# Indication.net
KiCad netlist of a schematic drawn in Altium Designer
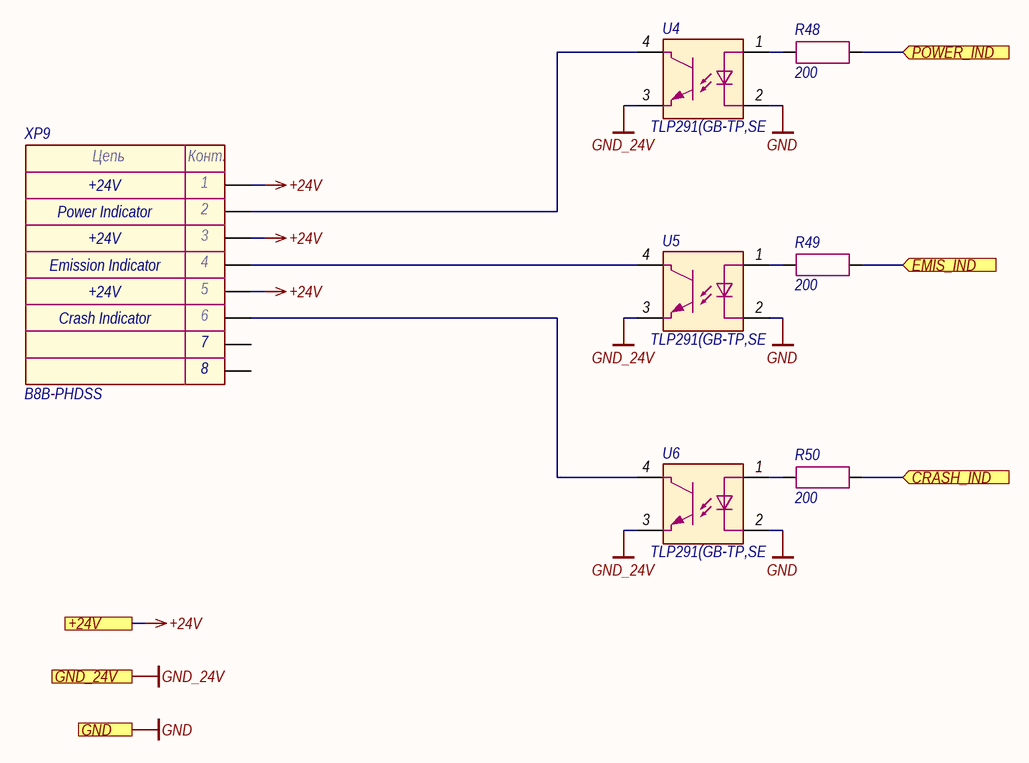
[diagram p0: Indication.SchDoc]

(export (version "E")
  (design (tool "Eeschema 10.0.6"))
  (components
    (comp (ref "R48")
      (value "200")
      (footprint "Pcb_library:RES_0603")
      (fields (field (name "MANUFACTURER") "Yageo"))
      (libsource (lib "Schem_library") (part "Resistor"))
    )
    (comp (ref "R49")
      (value "200")
      (footprint "Pcb_library:RES_0603")
      (fields (field (name "MANUFACTURER") "Yageo"))
      (libsource (lib "Schem_library") (part "Resistor"))
    )
    (comp (ref "R50")
      (value "200")
      (footprint "Pcb_library:RES_0603")
      (fields (field (name "MANUFACTURER") "Yageo"))
      (libsource (lib "Schem_library") (part "Resistor"))
    )
    (comp (ref "U4")
      (value "TLP291(GB-TP,SE")
      (footprint "Pcb_library:11-3C1")
      (fields (field (name "MANUFACTURER") "Toshiba"))
      (libsource (lib "Schem_library") (part "TLP291"))
    )
    (comp (ref "U5")
      (value "TLP291(GB-TP,SE")
      (footprint "Pcb_library:11-3C1")
      (fields (field (name "MANUFACTURER") "Toshiba"))
      (libsource (lib "Schem_library") (part "TLP291"))
    )
    (comp (ref "U6")
      (value "TLP291(GB-TP,SE")
      (footprint "Pcb_library:11-3C1")
      (fields (field (name "MANUFACTURER") "Toshiba"))
      (libsource (lib "Schem_library") (part "TLP291"))
    )
    (comp (ref "XP9")
      (value "B8B-PHDSS")
      (footprint "Pcb_library:B8B-PHDSS")
      (fields (field (name "MANUFACTURER") "JST"))
      (libsource (lib "Schem_library") (part "Connector-8"))
    )
  )
  (nets
    (net (code "1") (name "+24V") (class "Default")
      (node (ref "XP9") (pin "1") (pintype "passive"))
      (node (ref "XP9") (pin "3") (pintype "passive"))
      (node (ref "XP9") (pin "5") (pintype "passive"))
    )
    (net (code "2") (name "/CRASH_IND") (class "Default")
      (node (ref "R50") (pin "2") (pinfunction "2_2") (pintype "passive"))
    )
    (net (code "3") (name "/EMIS_IND") (class "Default")
      (node (ref "R49") (pin "2") (pinfunction "2_2") (pintype "passive"))
    )
    (net (code "4") (name "/POWER_IND") (class "Default")
      (node (ref "R48") (pin "2") (pinfunction "2_2") (pintype "passive"))
    )
    (net (code "5") (name "GND") (class "Default")
      (node (ref "U4") (pin "2") (pintype "passive"))
      (node (ref "U5") (pin "2") (pintype "passive"))
      (node (ref "U6") (pin "2") (pintype "passive"))
    )
    (net (code "6") (name "GND_24V") (class "Default")
      (node (ref "U4") (pin "3") (pintype "passive"))
      (node (ref "U5") (pin "3") (pintype "passive"))
      (node (ref "U6") (pin "3") (pintype "passive"))
    )
    (net (code "7") (name "Net-(R48-Pad1)") (class "Default")
      (node (ref "R48") (pin "1") (pinfunction "1_1") (pintype "passive"))
      (node (ref "U4") (pin "1") (pintype "passive"))
    )
    (net (code "8") (name "Net-(R49-Pad1)") (class "Default")
      (node (ref "R49") (pin "1") (pinfunction "1_1") (pintype "passive"))
      (node (ref "U5") (pin "1") (pintype "passive"))
    )
    (net (code "9") (name "Net-(R50-Pad1)") (class "Default")
      (node (ref "R50") (pin "1") (pinfunction "1_1") (pintype "passive"))
      (node (ref "U6") (pin "1") (pintype "passive"))
    )
    (net (code "10") (name "Net-(U4-Pad4)") (class "Default")
      (node (ref "U4") (pin "4") (pintype "passive"))
      (node (ref "XP9") (pin "2") (pintype "passive"))
    )
    (net (code "11") (name "Net-(U5-Pad4)") (class "Default")
      (node (ref "U5") (pin "4") (pintype "passive"))
      (node (ref "XP9") (pin "4") (pintype "passive"))
    )
    (net (code "12") (name "Net-(U6-Pad4)") (class "Default")
      (node (ref "U6") (pin "4") (pintype "passive"))
      (node (ref "XP9") (pin "6") (pintype "passive"))
    )
    (net (code "13") (name "unconnected-(XP9-Pad7)") (class "Default")
      (node (ref "XP9") (pin "7") (pintype "passive"))
    )
    (net (code "14") (name "unconnected-(XP9-Pad8)") (class "Default")
      (node (ref "XP9") (pin "8") (pintype "passive"))
    )
  )
)
